# SCH.net
KiCad netlist of a schematic drawn in EasyEDA
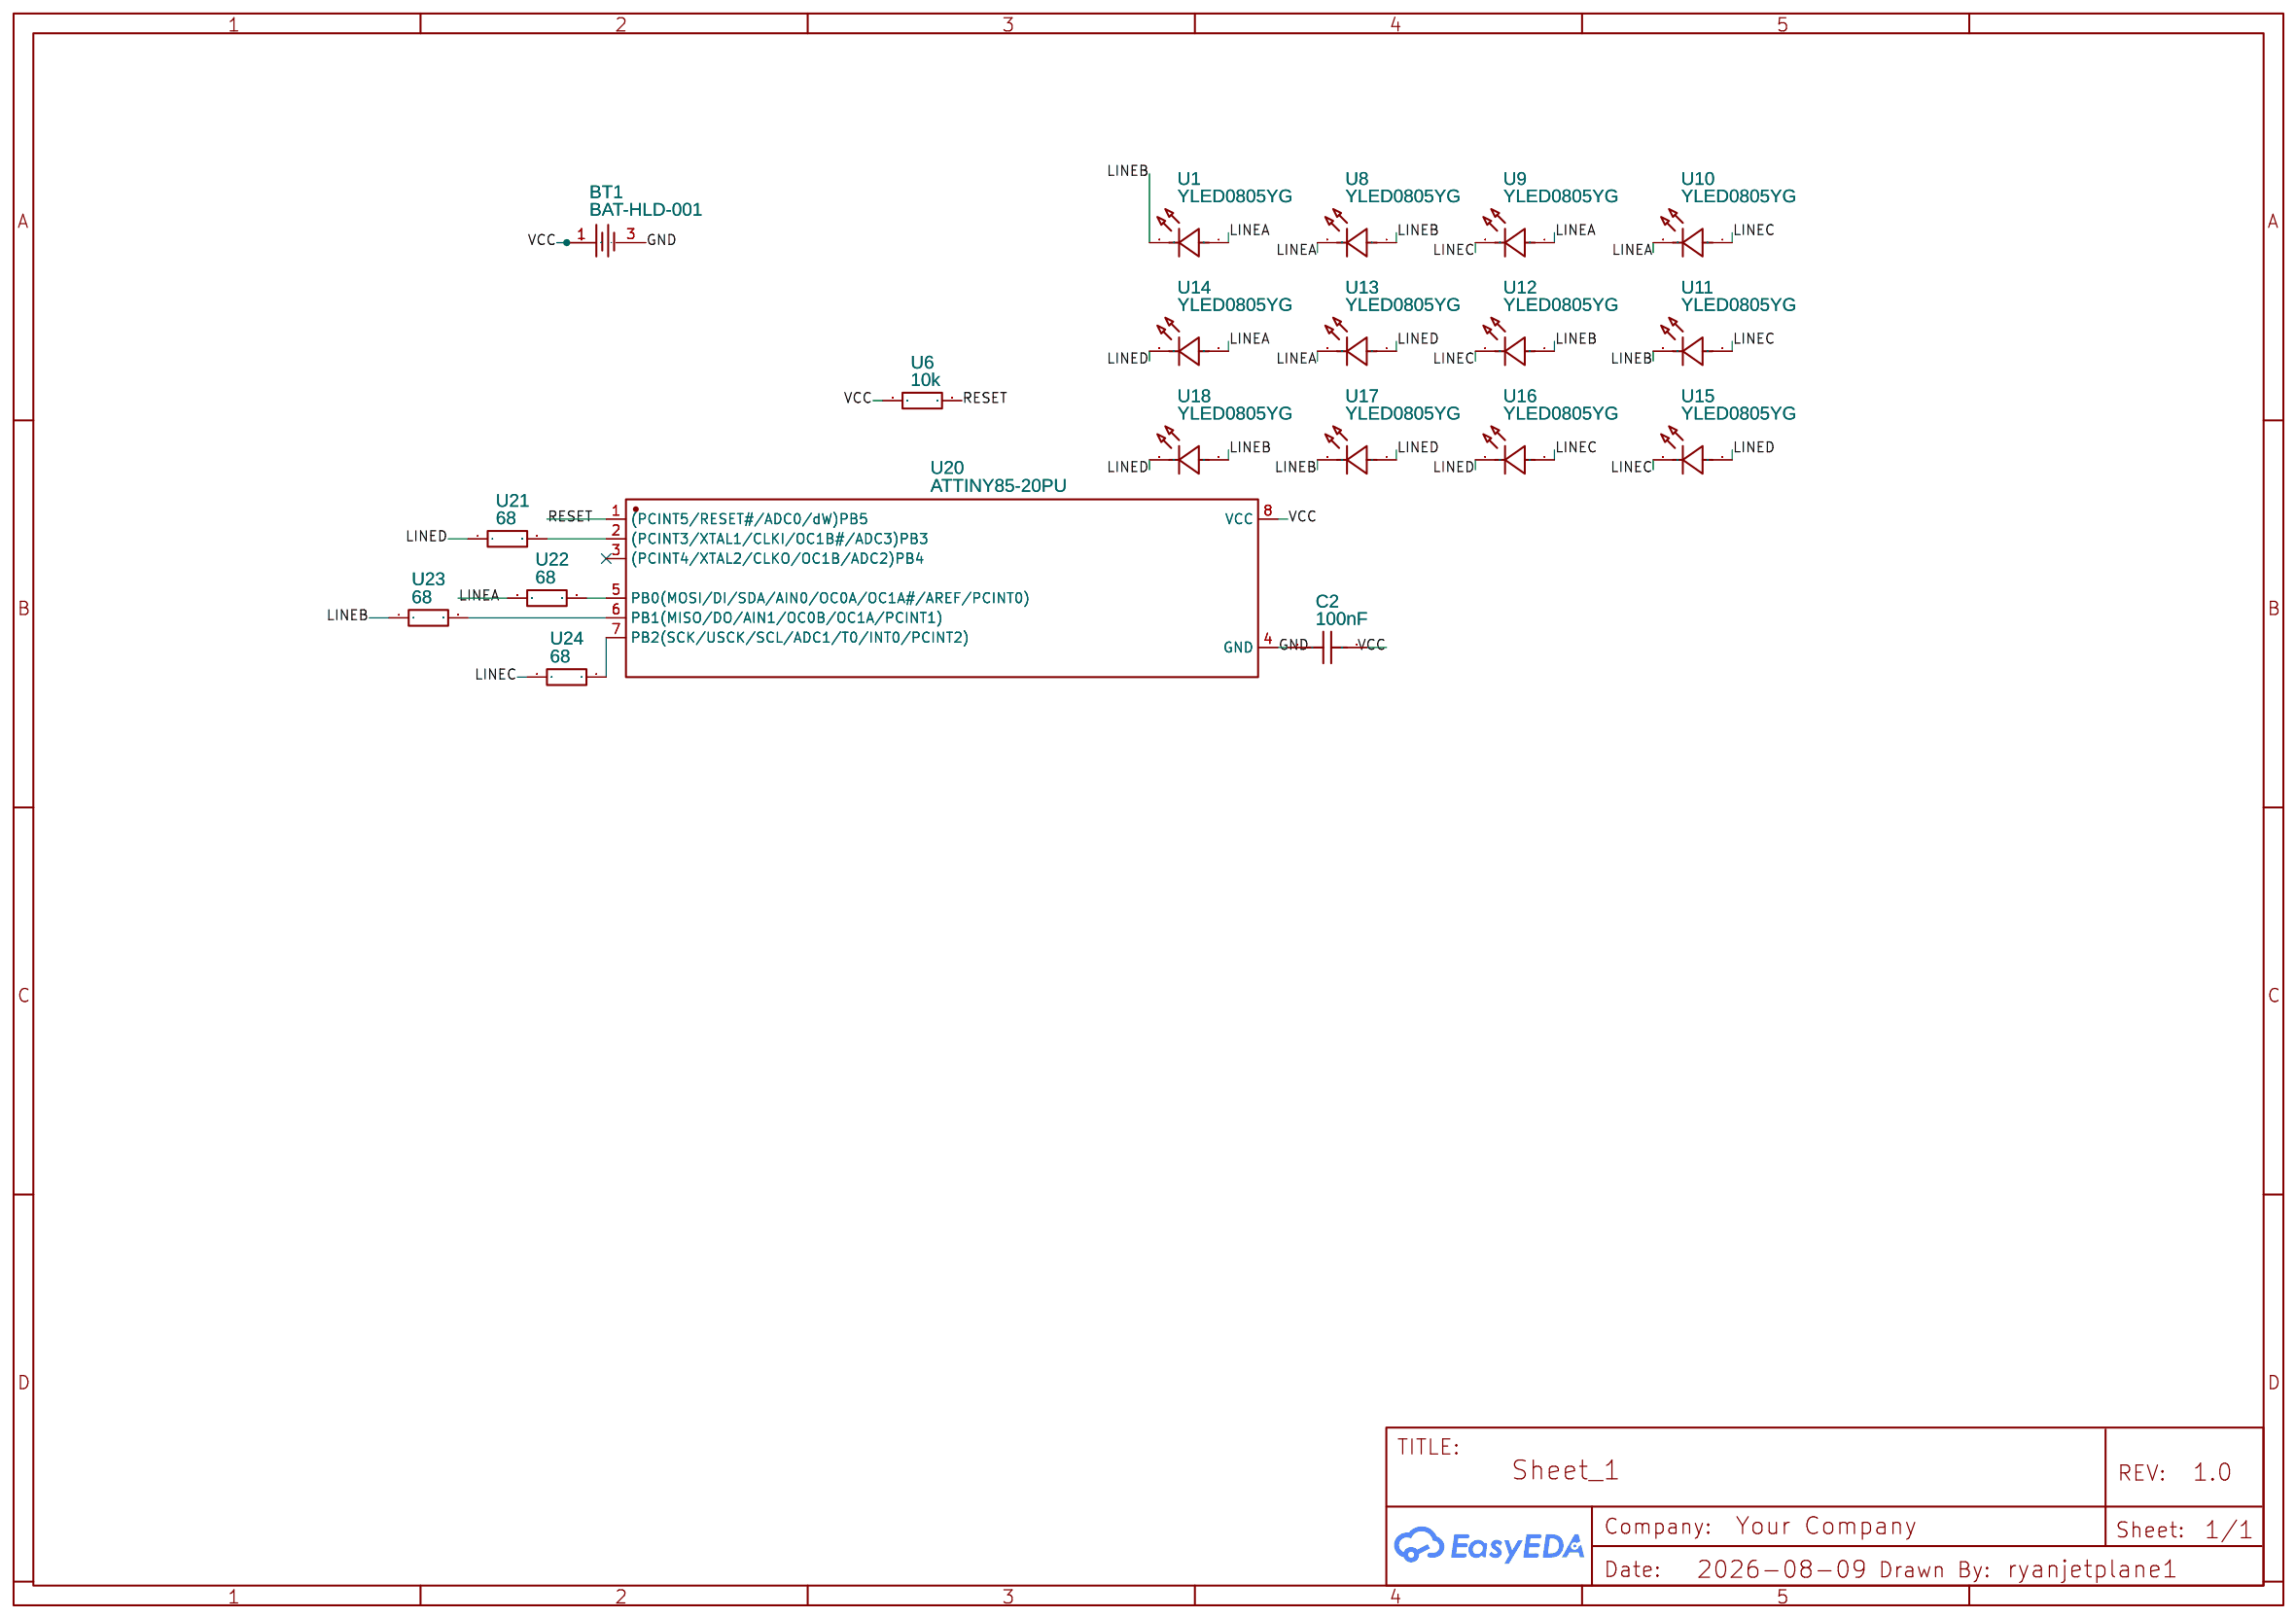
[diagram p0: schematic sheet]

(export (version "E")
  (design (tool "Eeschema 10.0.6"))
  (components
    (comp (ref "BT1")
      (value "BAT-HLD-001")
      (fields (field (name "Manufacturer") "TE Connectivity(泰科电子)"))
      (libsource (lib "") (part "BAT-HLD-001"))
    )
    (comp (ref "C2")
      (value "100nF")
      (fields
        (field (name "Manufacturer Part") "TCC0805X7R104M500DTS")
        (field (name "Manufacturer") "CCTC(三环)")
      )
      (libsource (lib "") (part "TCC0805X7R104M500DTS"))
    )
    (comp (ref "U1")
      (value "YLED0805YG")
      (fields (field (name "Manufacturer") "YONGYUTAI(永裕泰)"))
      (libsource (lib "") (part "YLED0805YG"))
    )
    (comp (ref "U6")
      (value "10k")
      (fields (field (name "Manufacturer Part") "WSL0805R0260FEA") (field (name "Manufacturer") "VISHAY(威世)"))
      (libsource (lib "") (part "WSL0805R0260FEA"))
    )
    (comp (ref "U8")
      (value "YLED0805YG")
      (fields (field (name "Manufacturer") "YONGYUTAI(永裕泰)"))
      (libsource (lib "") (part "YLED0805YG"))
    )
    (comp (ref "U9")
      (value "YLED0805YG")
      (fields (field (name "Manufacturer") "YONGYUTAI(永裕泰)"))
      (libsource (lib "") (part "YLED0805YG"))
    )
    (comp (ref "U10")
      (value "YLED0805YG")
      (fields (field (name "Manufacturer") "YONGYUTAI(永裕泰)"))
      (libsource (lib "") (part "YLED0805YG"))
    )
    (comp (ref "U11")
      (value "YLED0805YG")
      (fields (field (name "Manufacturer") "YONGYUTAI(永裕泰)"))
      (libsource (lib "") (part "YLED0805YG"))
    )
    (comp (ref "U12")
      (value "YLED0805YG")
      (fields (field (name "Manufacturer") "YONGYUTAI(永裕泰)"))
      (libsource (lib "") (part "YLED0805YG"))
    )
    (comp (ref "U13")
      (value "YLED0805YG")
      (fields (field (name "Manufacturer") "YONGYUTAI(永裕泰)"))
      (libsource (lib "") (part "YLED0805YG"))
    )
    (comp (ref "U14")
      (value "YLED0805YG")
      (fields (field (name "Manufacturer") "YONGYUTAI(永裕泰)"))
      (libsource (lib "") (part "YLED0805YG"))
    )
    (comp (ref "U15")
      (value "YLED0805YG")
      (fields (field (name "Manufacturer") "YONGYUTAI(永裕泰)"))
      (libsource (lib "") (part "YLED0805YG"))
    )
    (comp (ref "U16")
      (value "YLED0805YG")
      (fields (field (name "Manufacturer") "YONGYUTAI(永裕泰)"))
      (libsource (lib "") (part "YLED0805YG"))
    )
    (comp (ref "U17")
      (value "YLED0805YG")
      (fields (field (name "Manufacturer") "YONGYUTAI(永裕泰)"))
      (libsource (lib "") (part "YLED0805YG"))
    )
    (comp (ref "U18")
      (value "YLED0805YG")
      (fields (field (name "Manufacturer") "YONGYUTAI(永裕泰)"))
      (libsource (lib "") (part "YLED0805YG"))
    )
    (comp (ref "U20")
      (value "ATTINY85-20PU")
      (fields (field (name "Manufacturer") "MICROCHIP(美国微芯)"))
      (libsource (lib "") (part "ATTINY85-20PU"))
    )
    (comp (ref "U21")
      (value "68")
      (fields (field (name "Manufacturer Part") "WSL0805R0260FEA") (field (name "Manufacturer") "VISHAY(威世)"))
      (libsource (lib "") (part "WSL0805R0260FEA"))
    )
    (comp (ref "U22")
      (value "68")
      (fields (field (name "Manufacturer Part") "WSL0805R0260FEA") (field (name "Manufacturer") "VISHAY(威世)"))
      (libsource (lib "") (part "WSL0805R0260FEA"))
    )
    (comp (ref "U23")
      (value "68")
      (fields (field (name "Manufacturer Part") "WSL0805R0260FEA") (field (name "Manufacturer") "VISHAY(威世)"))
      (libsource (lib "") (part "WSL0805R0260FEA"))
    )
    (comp (ref "U24")
      (value "68")
      (fields (field (name "Manufacturer Part") "WSL0805R0260FEA") (field (name "Manufacturer") "VISHAY(威世)"))
      (libsource (lib "") (part "WSL0805R0260FEA_1"))
    )
  )
  (nets
    (net (code "1") (name "/GND") (class "Default")
      (node (ref "BT1") (pin "3") (pinfunction "-_3") (pintype "input"))
      (node (ref "C2") (pin "1") (pinfunction "1_1") (pintype "unspecified"))
      (node (ref "U20") (pin "4") (pinfunction "GND_4") (pintype "unspecified"))
    )
    (net (code "2") (name "/LINEA") (class "Default")
      (node (ref "U1") (pin "1") (pinfunction "1_1") (pintype "unspecified"))
      (node (ref "U10") (pin "2") (pinfunction "2_2") (pintype "unspecified"))
      (node (ref "U13") (pin "2") (pinfunction "2_2") (pintype "unspecified"))
      (node (ref "U14") (pin "1") (pinfunction "1_1") (pintype "unspecified"))
      (node (ref "U22") (pin "1") (pinfunction "1_1") (pintype "unspecified"))
      (node (ref "U8") (pin "2") (pinfunction "2_2") (pintype "unspecified"))
      (node (ref "U9") (pin "1") (pinfunction "1_1") (pintype "unspecified"))
    )
    (net (code "3") (name "/LINEB") (class "Default")
      (node (ref "U1") (pin "2") (pinfunction "2_2") (pintype "unspecified"))
      (node (ref "U11") (pin "2") (pinfunction "2_2") (pintype "unspecified"))
      (node (ref "U12") (pin "1") (pinfunction "1_1") (pintype "unspecified"))
      (node (ref "U17") (pin "2") (pinfunction "2_2") (pintype "unspecified"))
      (node (ref "U18") (pin "1") (pinfunction "1_1") (pintype "unspecified"))
      (node (ref "U23") (pin "1") (pinfunction "1_1") (pintype "unspecified"))
      (node (ref "U8") (pin "1") (pinfunction "1_1") (pintype "unspecified"))
    )
    (net (code "4") (name "/LINEC") (class "Default")
      (node (ref "U10") (pin "1") (pinfunction "1_1") (pintype "unspecified"))
      (node (ref "U11") (pin "1") (pinfunction "1_1") (pintype "unspecified"))
      (node (ref "U12") (pin "2") (pinfunction "2_2") (pintype "unspecified"))
      (node (ref "U15") (pin "2") (pinfunction "2_2") (pintype "unspecified"))
      (node (ref "U16") (pin "1") (pinfunction "1_1") (pintype "unspecified"))
      (node (ref "U24") (pin "2") (pinfunction "2_2") (pintype "unspecified"))
      (node (ref "U9") (pin "2") (pinfunction "2_2") (pintype "unspecified"))
    )
    (net (code "5") (name "/LINED") (class "Default")
      (node (ref "U13") (pin "1") (pinfunction "1_1") (pintype "unspecified"))
      (node (ref "U14") (pin "2") (pinfunction "2_2") (pintype "unspecified"))
      (node (ref "U15") (pin "1") (pinfunction "1_1") (pintype "unspecified"))
      (node (ref "U16") (pin "2") (pinfunction "2_2") (pintype "unspecified"))
      (node (ref "U17") (pin "1") (pinfunction "1_1") (pintype "unspecified"))
      (node (ref "U18") (pin "2") (pinfunction "2_2") (pintype "unspecified"))
      (node (ref "U21") (pin "1") (pinfunction "1_1") (pintype "unspecified"))
    )
    (net (code "6") (name "/RESET") (class "Default")
      (node (ref "U20") (pin "1") (pinfunction "(PCINT5/RESET#/ADC0/dW)PB5_1") (pintype "unspecified"))
      (node (ref "U6") (pin "2") (pinfunction "2_2") (pintype "unspecified"))
    )
    (net (code "7") (name "/VCC") (class "Default")
      (node (ref "BT1") (pin "1") (pinfunction "+_1") (pintype "input"))
      (node (ref "BT1") (pin "2") (pinfunction "+_2") (pintype "input"))
      (node (ref "C2") (pin "2") (pinfunction "2_2") (pintype "unspecified"))
      (node (ref "U20") (pin "8") (pinfunction "VCC_8") (pintype "unspecified"))
      (node (ref "U6") (pin "1") (pinfunction "1_1") (pintype "unspecified"))
    )
    (net (code "8") (name "Net-(U20-(PCINT3{slash}XTAL1{slash}CLKI{slash}OC1B#{slash}ADC3)PB3)") (class "Default")
      (node (ref "U20") (pin "2") (pinfunction "(PCINT3/XTAL1/CLKI/OC1B#/ADC3)PB3_2") (pintype "unspecified"))
      (node (ref "U21") (pin "2") (pinfunction "2_2") (pintype "unspecified"))
    )
    (net (code "9") (name "Net-(U20-PB0(MOSI{slash}DI{slash}SDA{slash}AIN0{slash}OC0A{slash}OC1A#{slash}AREF{slash}PCINT0))") (class "Default")
      (node (ref "U20") (pin "5") (pinfunction "PB0(MOSI/DI/SDA/AIN0/OC0A/OC1A#/AREF/PCINT0)_5") (pintype "unspecified"))
      (node (ref "U22") (pin "2") (pinfunction "2_2") (pintype "unspecified"))
    )
    (net (code "10") (name "Net-(U20-PB1(MISO{slash}DO{slash}AIN1{slash}OC0B{slash}OC1A{slash}PCINT1))") (class "Default")
      (node (ref "U20") (pin "6") (pinfunction "PB1(MISO/DO/AIN1/OC0B/OC1A/PCINT1)_6") (pintype "unspecified"))
      (node (ref "U23") (pin "2") (pinfunction "2_2") (pintype "unspecified"))
    )
    (net (code "11") (name "Net-(U20-PB2(SCK{slash}USCK{slash}SCL{slash}ADC1{slash}T0{slash}INT0{slash}PCINT2))") (class "Default")
      (node (ref "U20") (pin "7") (pinfunction "PB2(SCK/USCK/SCL/ADC1/T0/INT0/PCINT2)_7") (pintype "unspecified"))
      (node (ref "U24") (pin "1") (pinfunction "1_1") (pintype "unspecified"))
    )
    (net (code "12") (name "unconnected-(U20-(PCINT4{slash}XTAL2{slash}CLKO{slash}OC1B{slash}ADC2)PB4-Pad3)") (class "Default")
      (node (ref "U20") (pin "3") (pinfunction "(PCINT4/XTAL2/CLKO/OC1B/ADC2)PB4_3") (pintype "unspecified+no_connect"))
    )
  )
)
